# untitled2.net
KiCad netlist of a schematic drawn in EAGLE
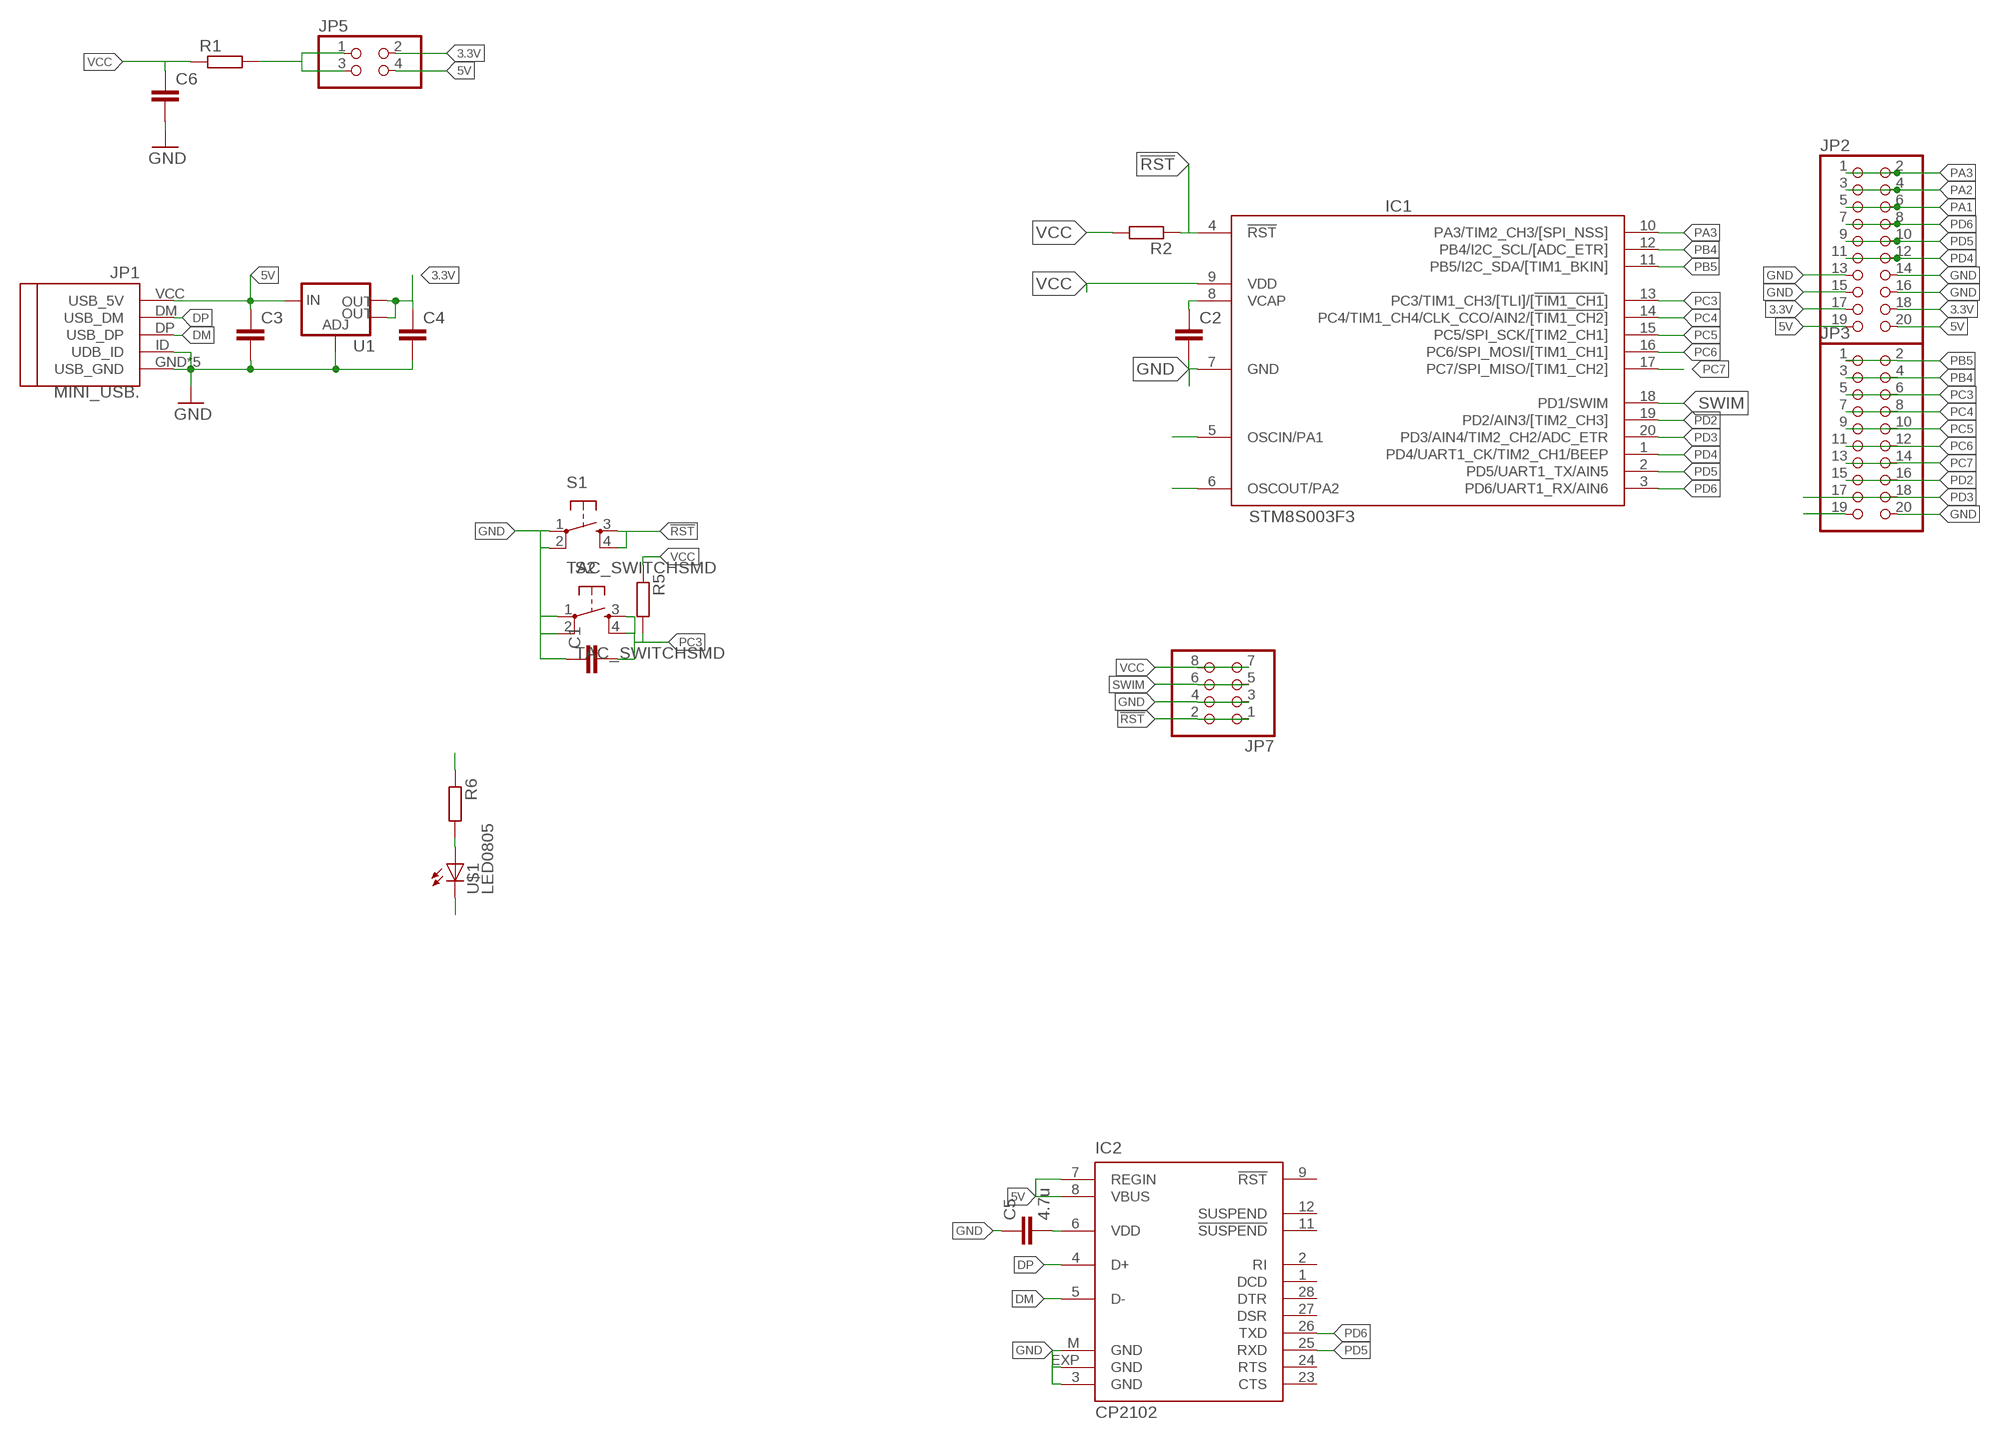
[diagram p0: schematic, sheet 1]

(export (version "E")
  (design (tool "Eeschema 10.0.6"))
  (components
    (comp (ref "C1")
      (value "CC0805")
      (footprint "eagle-import:C0805")
      (libsource (lib "eagle-import") (part "CC0805"))
    )
    (comp (ref "C2")
      (value "CC0603")
      (footprint "eagle-import:C0603")
      (libsource (lib "eagle-import") (part "CC0603"))
    )
    (comp (ref "C3")
      (value "CC0805")
      (footprint "eagle-import:C0805")
      (libsource (lib "eagle-import") (part "CC0805"))
    )
    (comp (ref "C4")
      (value "CC0805")
      (footprint "eagle-import:C0805")
      (libsource (lib "eagle-import") (part "CC0805"))
    )
    (comp (ref "C5")
      (value "4.7u")
      (footprint "eagle-import:C0603")
      (libsource (lib "eagle-import") (part "CC0603"))
    )
    (comp (ref "C6")
      (value "CC0805")
      (footprint "eagle-import:C0805")
      (libsource (lib "eagle-import") (part "CC0805"))
    )
    (comp (ref "IC1")
      (value "STM8S003F3")
      (footprint "eagle-import:TSSOP20")
      (libsource (lib "eagle-import") (part "STM8S003F3"))
    )
    (comp (ref "IC2")
      (value "CP2102")
      (footprint "eagle-import:MLP28")
      (fields (field (name "MF") "FARNELL") (field (name "MPN") "CP2102-GM"))
      (libsource (lib "eagle-import") (part "CP2102"))
    )
    (comp (ref "JP1")
      (value "MINI_USB.")
      (footprint "eagle-import:32005-201")
      (libsource (lib "eagle-import") (part "MINI_USB."))
    )
    (comp (ref "JP2")
      (value "PINHD-2X10_2.54-SMD")
      (footprint "eagle-import:2X10SMD")
      (libsource (lib "eagle-import") (part "PINHD-2X10_2.54-SMD"))
    )
    (comp (ref "JP3")
      (value "PINHD-2X10_2.54-SMD")
      (footprint "eagle-import:2X10SMD")
      (libsource (lib "eagle-import") (part "PINHD-2X10_2.54-SMD"))
    )
    (comp (ref "JP5")
      (value "PINHD-2X02_2.54-SMD")
      (footprint "eagle-import:2X02SMD")
      (libsource (lib "eagle-import") (part "PINHD-2X02_2.54-SMD"))
    )
    (comp (ref "JP7")
      (value "PINHD-2X04_2.54-SMD")
      (footprint "eagle-import:2X04SMD")
      (libsource (lib "eagle-import") (part "PINHD-2X04_2.54-SMD"))
    )
    (comp (ref "R1")
      (value "R1206")
      (footprint "eagle-import:R1206")
      (libsource (lib "eagle-import") (part "R1206"))
    )
    (comp (ref "R2")
      (value "R0603")
      (footprint "eagle-import:0603")
      (libsource (lib "eagle-import") (part "R0603"))
    )
    (comp (ref "R5")
      (value "R0805")
      (footprint "eagle-import:R0805")
      (libsource (lib "eagle-import") (part "R0805"))
    )
    (comp (ref "R6")
      (value "R0805")
      (footprint "eagle-import:R0805")
      (libsource (lib "eagle-import") (part "R0805"))
    )
    (comp (ref "S1")
      (value "TAC_SWITCHSMD")
      (footprint "eagle-import:TACTILE-SWITCH-SMD")
      (libsource (lib "eagle-import") (part "TAC_SWITCHSMD"))
    )
    (comp (ref "S2")
      (value "TAC_SWITCHSMD")
      (footprint "eagle-import:TACTILE-SWITCH-SMD")
      (libsource (lib "eagle-import") (part "TAC_SWITCHSMD"))
    )
    (comp (ref "U$1")
      (value "LED0805")
      (footprint "eagle-import:0805-LED")
      (libsource (lib "eagle-import") (part "LED0805"))
    )
    (comp (ref "U1")
      (value "V_REG_LM1117SOT223")
      (footprint "eagle-import:SOT223")
      (libsource (lib "eagle-import") (part "V_REG_LM1117SOT223"))
    )
  )
  (nets
    (net (code "1") (name "/~{RST}") (class "Default")
      (node (ref "IC1") (pin "4") (pinfunction "~{RST}_4") (pintype "input"))
      (node (ref "JP7") (pin "1") (pinfunction "1_1") (pintype "passive"))
      (node (ref "JP7") (pin "2") (pinfunction "2_2") (pintype "passive"))
      (node (ref "R2") (pin "1") (pinfunction "1_1") (pintype "passive"))
      (node (ref "S1") (pin "3") (pinfunction "3_3") (pintype "passive"))
      (node (ref "S1") (pin "4") (pinfunction "4_4") (pintype "passive"))
    )
    (net (code "2") (name "3.3V") (class "Default")
      (node (ref "C4") (pin "1") (pinfunction "1_1") (pintype "passive"))
      (node (ref "JP2") (pin "17") (pinfunction "17_17") (pintype "passive"))
      (node (ref "JP2") (pin "18") (pinfunction "18_18") (pintype "passive"))
      (node (ref "JP5") (pin "2") (pinfunction "2_2") (pintype "passive"))
      (node (ref "U1") (pin "2") (pinfunction "OUT_2") (pintype "output"))
      (node (ref "U1") (pin "4") (pinfunction "OUT_4") (pintype "output"))
    )
    (net (code "3") (name "5V") (class "Default")
      (node (ref "C3") (pin "1") (pinfunction "1_1") (pintype "passive"))
      (node (ref "IC2") (pin "7") (pinfunction "REGIN_7") (pintype "passive"))
      (node (ref "IC2") (pin "8") (pinfunction "VBUS_8") (pintype "input"))
      (node (ref "JP1") (pin "VCC") (pinfunction "USB_5V_VCC") (pintype "power_in"))
      (node (ref "JP2") (pin "19") (pinfunction "19_19") (pintype "passive"))
      (node (ref "JP2") (pin "20") (pinfunction "20_20") (pintype "passive"))
      (node (ref "JP5") (pin "4") (pinfunction "4_4") (pintype "passive"))
      (node (ref "U1") (pin "3") (pinfunction "IN_3") (pintype "input"))
    )
    (net (code "4") (name "DM") (class "Default")
      (node (ref "IC2") (pin "5") (pinfunction "D-_5") (pintype "bidirectional"))
      (node (ref "JP1") (pin "DP") (pinfunction "USB_DP_DP") (pintype "bidirectional"))
    )
    (net (code "5") (name "DP") (class "Default")
      (node (ref "IC2") (pin "4") (pinfunction "D+_4") (pintype "bidirectional"))
      (node (ref "JP1") (pin "DM") (pinfunction "USB_DM_DM") (pintype "bidirectional"))
    )
    (net (code "6") (name "GND") (class "Default")
      (node (ref "C1") (pin "1") (pinfunction "1_1") (pintype "passive"))
      (node (ref "C2") (pin "2") (pinfunction "2_2") (pintype "passive"))
      (node (ref "C3") (pin "2") (pinfunction "2_2") (pintype "passive"))
      (node (ref "C4") (pin "2") (pinfunction "2_2") (pintype "passive"))
      (node (ref "C5") (pin "1") (pinfunction "1_1") (pintype "passive"))
      (node (ref "C6") (pin "2") (pinfunction "2_2") (pintype "passive"))
      (node (ref "IC1") (pin "7") (pinfunction "GND_7") (pintype "power_in"))
      (node (ref "IC2") (pin "3") (pinfunction "GND_3") (pintype "power_in"))
      (node (ref "IC2") (pin "EXP") (pinfunction "GND_EXP") (pintype "power_in"))
      (node (ref "IC2") (pin "M") (pinfunction "GND_M") (pintype "power_in"))
      (node (ref "JP1") (pin "GND") (pinfunction "USB_GND_GND") (pintype "power_in"))
      (node (ref "JP1") (pin "ID") (pinfunction "UDB_ID_ID") (pintype "bidirectional"))
      (node (ref "JP1") (pin "M1") (pinfunction "USB_GND_M1") (pintype "power_in"))
      (node (ref "JP1") (pin "M2") (pinfunction "USB_GND_M2") (pintype "power_in"))
      (node (ref "JP1") (pin "M3") (pinfunction "USB_GND_M3") (pintype "power_in"))
      (node (ref "JP1") (pin "M4") (pinfunction "USB_GND_M4") (pintype "power_in"))
      (node (ref "JP2") (pin "13") (pinfunction "13_13") (pintype "passive"))
      (node (ref "JP2") (pin "14") (pinfunction "14_14") (pintype "passive"))
      (node (ref "JP2") (pin "15") (pinfunction "15_15") (pintype "passive"))
      (node (ref "JP2") (pin "16") (pinfunction "16_16") (pintype "passive"))
      (node (ref "JP3") (pin "19") (pinfunction "19_19") (pintype "passive"))
      (node (ref "JP3") (pin "20") (pinfunction "20_20") (pintype "passive"))
      (node (ref "JP7") (pin "3") (pinfunction "3_3") (pintype "passive"))
      (node (ref "JP7") (pin "4") (pinfunction "4_4") (pintype "passive"))
      (node (ref "S1") (pin "1") (pinfunction "1_1") (pintype "passive"))
      (node (ref "S1") (pin "2") (pinfunction "2_2") (pintype "passive"))
      (node (ref "S2") (pin "1") (pinfunction "1_1") (pintype "passive"))
      (node (ref "S2") (pin "2") (pinfunction "2_2") (pintype "passive"))
      (node (ref "U$1") (pin "C") (pinfunction "C_C") (pintype "passive"))
      (node (ref "U1") (pin "1") (pinfunction "ADJ_1") (pintype "input"))
    )
    (net (code "7") (name "Net-(IC1-VCAP)") (class "Default")
      (node (ref "C2") (pin "1") (pinfunction "1_1") (pintype "passive"))
      (node (ref "IC1") (pin "8") (pinfunction "VCAP_8") (pintype "power_in"))
    )
    (net (code "8") (name "Net-(IC2-VDD)") (class "Default")
      (node (ref "C5") (pin "2") (pinfunction "2_2") (pintype "passive"))
      (node (ref "IC2") (pin "6") (pinfunction "VDD_6") (pintype "power_in"))
    )
    (net (code "9") (name "Net-(R6-Pad2)") (class "Default")
      (node (ref "R6") (pin "2") (pinfunction "2_2") (pintype "passive"))
      (node (ref "U$1") (pin "A") (pinfunction "A_A") (pintype "passive"))
    )
    (net (code "10") (name "PA1") (class "Default")
      (node (ref "IC1") (pin "5") (pinfunction "OSCIN/PA1_5") (pintype "bidirectional"))
      (node (ref "JP2") (pin "5") (pinfunction "5_5") (pintype "passive"))
      (node (ref "JP2") (pin "6") (pinfunction "6_6") (pintype "passive"))
    )
    (net (code "11") (name "PA2") (class "Default")
      (node (ref "IC1") (pin "6") (pinfunction "OSCOUT/PA2_6") (pintype "bidirectional"))
      (node (ref "JP2") (pin "3") (pinfunction "3_3") (pintype "passive"))
      (node (ref "JP2") (pin "4") (pinfunction "4_4") (pintype "passive"))
    )
    (net (code "12") (name "PA3") (class "Default")
      (node (ref "IC1") (pin "10") (pinfunction "PA3/TIM2_CH3/[SPI_NSS]_10") (pintype "bidirectional"))
      (node (ref "JP2") (pin "1") (pinfunction "1_1") (pintype "passive"))
      (node (ref "JP2") (pin "2") (pinfunction "2_2") (pintype "passive"))
    )
    (net (code "13") (name "PB4") (class "Default")
      (node (ref "IC1") (pin "12") (pinfunction "PB4/I2C_SCL/[ADC_ETR]_12") (pintype "bidirectional"))
      (node (ref "JP3") (pin "3") (pinfunction "3_3") (pintype "passive"))
      (node (ref "JP3") (pin "4") (pinfunction "4_4") (pintype "passive"))
    )
    (net (code "14") (name "PB5") (class "Default")
      (node (ref "IC1") (pin "11") (pinfunction "PB5/I2C_SDA/[TIM1_BKIN]_11") (pintype "bidirectional"))
      (node (ref "JP3") (pin "1") (pinfunction "1_1") (pintype "passive"))
      (node (ref "JP3") (pin "2") (pinfunction "2_2") (pintype "passive"))
    )
    (net (code "15") (name "PC3") (class "Default")
      (node (ref "C1") (pin "2") (pinfunction "2_2") (pintype "passive"))
      (node (ref "IC1") (pin "13") (pinfunction "PC3/TIM1_CH3/[TLI]/[~{TIM1_CH1}]_13") (pintype "bidirectional"))
      (node (ref "JP3") (pin "5") (pinfunction "5_5") (pintype "passive"))
      (node (ref "JP3") (pin "6") (pinfunction "6_6") (pintype "passive"))
      (node (ref "R5") (pin "2") (pinfunction "2_2") (pintype "passive"))
      (node (ref "S2") (pin "3") (pinfunction "3_3") (pintype "passive"))
      (node (ref "S2") (pin "4") (pinfunction "4_4") (pintype "passive"))
    )
    (net (code "16") (name "PC4") (class "Default")
      (node (ref "IC1") (pin "14") (pinfunction "PC4/TIM1_CH4/CLK_CCO/AIN2/[~{TIM1_CH2}]_14") (pintype "bidirectional"))
      (node (ref "JP3") (pin "7") (pinfunction "7_7") (pintype "passive"))
      (node (ref "JP3") (pin "8") (pinfunction "8_8") (pintype "passive"))
    )
    (net (code "17") (name "PC5") (class "Default")
      (node (ref "IC1") (pin "15") (pinfunction "PC5/SPI_SCK/[TIM2_CH1]_15") (pintype "bidirectional"))
      (node (ref "JP3") (pin "10") (pinfunction "10_10") (pintype "passive"))
      (node (ref "JP3") (pin "9") (pinfunction "9_9") (pintype "passive"))
    )
    (net (code "18") (name "PC6") (class "Default")
      (node (ref "IC1") (pin "16") (pinfunction "PC6/SPI_MOSI/[TIM1_CH1]_16") (pintype "bidirectional"))
      (node (ref "JP3") (pin "11") (pinfunction "11_11") (pintype "passive"))
      (node (ref "JP3") (pin "12") (pinfunction "12_12") (pintype "passive"))
    )
    (net (code "19") (name "PC7") (class "Default")
      (node (ref "IC1") (pin "17") (pinfunction "PC7/SPI_MISO/[TIM1_CH2]_17") (pintype "bidirectional"))
      (node (ref "JP3") (pin "13") (pinfunction "13_13") (pintype "passive"))
      (node (ref "JP3") (pin "14") (pinfunction "14_14") (pintype "passive"))
    )
    (net (code "20") (name "PD2") (class "Default")
      (node (ref "IC1") (pin "19") (pinfunction "PD2/AIN3/[TIM2_CH3]_19") (pintype "bidirectional"))
      (node (ref "JP3") (pin "15") (pinfunction "15_15") (pintype "passive"))
      (node (ref "JP3") (pin "16") (pinfunction "16_16") (pintype "passive"))
    )
    (net (code "21") (name "PD3") (class "Default")
      (node (ref "IC1") (pin "20") (pinfunction "PD3/AIN4/TIM2_CH2/ADC_ETR_20") (pintype "bidirectional"))
      (node (ref "JP3") (pin "17") (pinfunction "17_17") (pintype "passive"))
      (node (ref "JP3") (pin "18") (pinfunction "18_18") (pintype "passive"))
    )
    (net (code "22") (name "PD4") (class "Default")
      (node (ref "IC1") (pin "1") (pinfunction "PD4/UART1_CK/TIM2_CH1/BEEP_1") (pintype "bidirectional"))
      (node (ref "JP2") (pin "11") (pinfunction "11_11") (pintype "passive"))
      (node (ref "JP2") (pin "12") (pinfunction "12_12") (pintype "passive"))
    )
    (net (code "23") (name "PD5") (class "Default")
      (node (ref "IC1") (pin "2") (pinfunction "PD5/UART1_TX/AIN5_2") (pintype "bidirectional"))
      (node (ref "IC2") (pin "25") (pinfunction "RXD_25") (pintype "input"))
      (node (ref "JP2") (pin "10") (pinfunction "10_10") (pintype "passive"))
      (node (ref "JP2") (pin "9") (pinfunction "9_9") (pintype "passive"))
    )
    (net (code "24") (name "PD6") (class "Default")
      (node (ref "IC1") (pin "3") (pinfunction "PD6/UART1_RX/AIN6_3") (pintype "bidirectional"))
      (node (ref "IC2") (pin "26") (pinfunction "TXD_26") (pintype "output"))
      (node (ref "JP2") (pin "7") (pinfunction "7_7") (pintype "passive"))
      (node (ref "JP2") (pin "8") (pinfunction "8_8") (pintype "passive"))
    )
    (net (code "25") (name "SWIM") (class "Default")
      (node (ref "IC1") (pin "18") (pinfunction "PD1/SWIM_18") (pintype "bidirectional"))
      (node (ref "JP7") (pin "5") (pinfunction "5_5") (pintype "passive"))
      (node (ref "JP7") (pin "6") (pinfunction "6_6") (pintype "passive"))
    )
    (net (code "26") (name "VCC") (class "Default")
      (node (ref "C6") (pin "1") (pinfunction "1_1") (pintype "passive"))
      (node (ref "IC1") (pin "9") (pinfunction "VDD_9") (pintype "power_in"))
      (node (ref "JP5") (pin "1") (pinfunction "1_1") (pintype "passive"))
      (node (ref "JP5") (pin "3") (pinfunction "3_3") (pintype "passive"))
      (node (ref "JP7") (pin "7") (pinfunction "7_7") (pintype "passive"))
      (node (ref "JP7") (pin "8") (pinfunction "8_8") (pintype "passive"))
      (node (ref "R1") (pin "1") (pinfunction "1_1") (pintype "passive"))
      (node (ref "R1") (pin "2") (pinfunction "2_2") (pintype "passive"))
      (node (ref "R2") (pin "2") (pinfunction "2_2") (pintype "passive"))
      (node (ref "R5") (pin "1") (pinfunction "1_1") (pintype "passive"))
      (node (ref "R6") (pin "1") (pinfunction "1_1") (pintype "passive"))
    )
    (net (code "27") (name "unconnected-(IC2-CTS-Pad23)") (class "Default")
      (node (ref "IC2") (pin "23") (pinfunction "CTS_23") (pintype "input"))
    )
    (net (code "28") (name "unconnected-(IC2-DCD-Pad1)") (class "Default")
      (node (ref "IC2") (pin "1") (pinfunction "DCD_1") (pintype "input"))
    )
    (net (code "29") (name "unconnected-(IC2-DSR-Pad27)") (class "Default")
      (node (ref "IC2") (pin "27") (pinfunction "DSR_27") (pintype "input"))
    )
    (net (code "30") (name "unconnected-(IC2-DTR-Pad28)") (class "Default")
      (node (ref "IC2") (pin "28") (pinfunction "DTR_28") (pintype "output"))
    )
    (net (code "31") (name "unconnected-(IC2-RI-Pad2)") (class "Default")
      (node (ref "IC2") (pin "2") (pinfunction "RI_2") (pintype "input"))
    )
    (net (code "32") (name "unconnected-(IC2-RTS-Pad24)") (class "Default")
      (node (ref "IC2") (pin "24") (pinfunction "RTS_24") (pintype "output"))
    )
    (net (code "33") (name "unconnected-(IC2-SUSPEND-Pad12)") (class "Default")
      (node (ref "IC2") (pin "12") (pinfunction "SUSPEND_12") (pintype "output"))
    )
    (net (code "34") (name "unconnected-(IC2-~{RST}-Pad9)") (class "Default")
      (node (ref "IC2") (pin "9") (pinfunction "~{RST}_9") (pintype "bidirectional"))
    )
    (net (code "35") (name "unconnected-(IC2-~{SUSPEND}-Pad11)") (class "Default")
      (node (ref "IC2") (pin "11") (pinfunction "~{SUSPEND}_11") (pintype "output"))
    )
  )
)
